# Human_Interface.net
KiCad netlist of a schematic drawn in Altium Designer
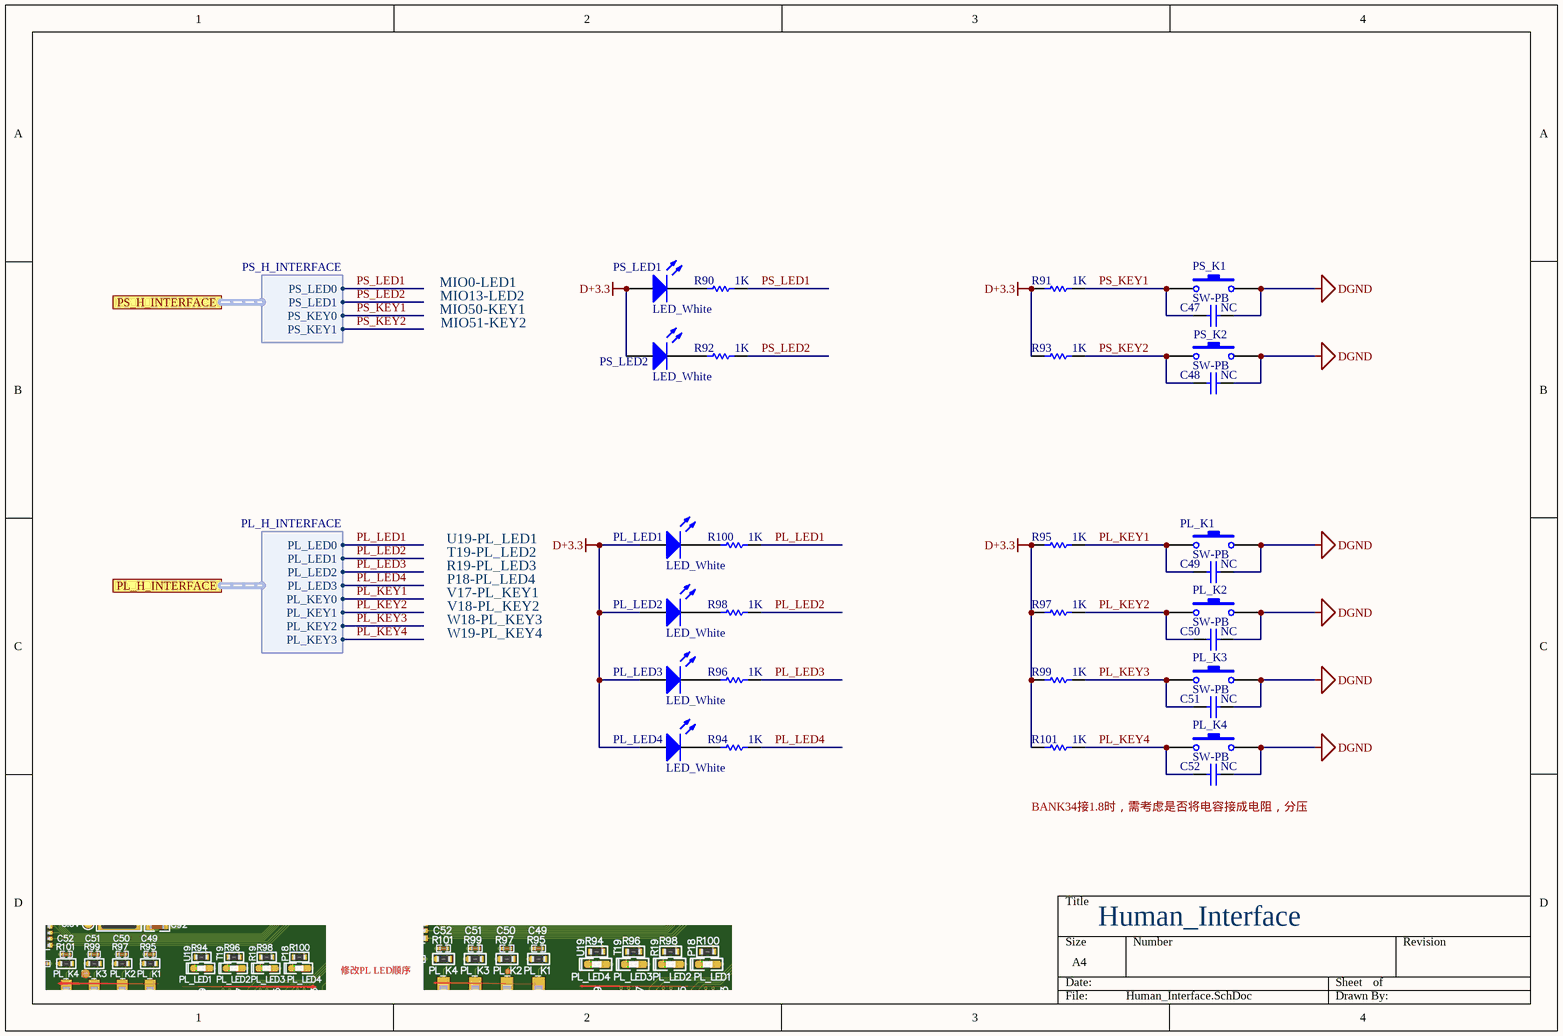
[diagram p0: Human_Interface.SchDoc]

(export (version "E")
  (design (tool "Eeschema 10.0.6"))
  (components
    (comp (ref "C47")
      (value "NC")
      (footprint "C 0402_LL")
      (description "Capacitor")
      (fields (field (name "PUBLISHER") "Altium Limited"))
      (libsource (lib "Miscellaneous Devices") (part "Cap"))
    )
    (comp (ref "C48")
      (value "NC")
      (footprint "C 0402_LL")
      (description "Capacitor")
      (fields (field (name "PUBLISHER") "Altium Limited"))
      (libsource (lib "Miscellaneous Devices") (part "Cap"))
    )
    (comp (ref "C49")
      (value "NC")
      (footprint "C 0402_LL")
      (description "Capacitor")
      (fields (field (name "PUBLISHER") "Altium Limited"))
      (libsource (lib "Miscellaneous Devices") (part "Cap"))
    )
    (comp (ref "C50")
      (value "NC")
      (footprint "C 0402_LL")
      (description "Capacitor")
      (fields (field (name "PUBLISHER") "Altium Limited"))
      (libsource (lib "Miscellaneous Devices") (part "Cap"))
    )
    (comp (ref "C51")
      (value "NC")
      (footprint "C 0402_LL")
      (description "Capacitor")
      (fields (field (name "PUBLISHER") "Altium Limited"))
      (libsource (lib "Miscellaneous Devices") (part "Cap"))
    )
    (comp (ref "C52")
      (value "NC")
      (footprint "C 0402_LL")
      (description "Capacitor")
      (fields (field (name "PUBLISHER") "Altium Limited"))
      (libsource (lib "Miscellaneous Devices") (part "Cap"))
    )
    (comp (ref "PL_K1")
      (value "SW-PB")
      (footprint "TSW SMD-3*6*4.3")
      (description "Switch")
      (fields (field (name "PUBLISHER") "Altium Limited"))
      (libsource (lib "Miscellaneous Devices") (part "SW-PB"))
    )
    (comp (ref "PL_K2")
      (value "SW-PB")
      (footprint "TSW SMD-3*6*4.3")
      (description "Switch")
      (fields (field (name "PUBLISHER") "Altium Limited"))
      (libsource (lib "Miscellaneous Devices") (part "SW-PB"))
    )
    (comp (ref "PL_K3")
      (value "SW-PB")
      (footprint "TSW SMD-3*6*4.3")
      (description "Switch")
      (fields (field (name "PUBLISHER") "Altium Limited"))
      (libsource (lib "Miscellaneous Devices") (part "SW-PB"))
    )
    (comp (ref "PL_K4")
      (value "SW-PB")
      (footprint "TSW SMD-3*6*4.3")
      (description "Switch")
      (fields (field (name "PUBLISHER") "Altium Limited"))
      (libsource (lib "Miscellaneous Devices") (part "SW-PB"))
    )
    (comp (ref "PL_LED1")
      (value "LED_White")
      (footprint "LED 0603W")
      (description "Typical INFRARED GaAs LED")
      (fields (field (name "PUBLISHER") "Altium Limited"))
      (libsource (lib "Miscellaneous Devices") (part "LED0"))
    )
    (comp (ref "PL_LED2")
      (value "LED_White")
      (footprint "LED 0603W")
      (description "Typical INFRARED GaAs LED")
      (fields (field (name "PUBLISHER") "Altium Limited"))
      (libsource (lib "Miscellaneous Devices") (part "LED0"))
    )
    (comp (ref "PL_LED3")
      (value "LED_White")
      (footprint "LED 0603W")
      (description "Typical INFRARED GaAs LED")
      (fields (field (name "PUBLISHER") "Altium Limited"))
      (libsource (lib "Miscellaneous Devices") (part "LED0"))
    )
    (comp (ref "PL_LED4")
      (value "LED_White")
      (footprint "LED 0603W")
      (description "Typical INFRARED GaAs LED")
      (fields (field (name "PUBLISHER") "Altium Limited"))
      (libsource (lib "Miscellaneous Devices") (part "LED0"))
    )
    (comp (ref "PS_K1")
      (value "SW-PB")
      (footprint "TSW SMD-3*6*4.3")
      (description "Switch")
      (fields (field (name "PUBLISHER") "Altium Limited"))
      (libsource (lib "Miscellaneous Devices") (part "SW-PB"))
    )
    (comp (ref "PS_K2")
      (value "SW-PB")
      (footprint "TSW SMD-3*6*4.3")
      (description "Switch")
      (fields (field (name "PUBLISHER") "Altium Limited"))
      (libsource (lib "Miscellaneous Devices") (part "SW-PB"))
    )
    (comp (ref "PS_LED1")
      (value "LED_White")
      (footprint "LED 0603W")
      (description "Typical INFRARED GaAs LED")
      (fields (field (name "PUBLISHER") "Altium Limited"))
      (libsource (lib "Miscellaneous Devices") (part "LED0"))
    )
    (comp (ref "PS_LED2")
      (value "LED_White")
      (footprint "LED 0603W")
      (description "Typical INFRARED GaAs LED")
      (fields (field (name "PUBLISHER") "Altium Limited"))
      (libsource (lib "Miscellaneous Devices") (part "LED0"))
    )
    (comp (ref "R90")
      (value "1K")
      (footprint "R 0603_L")
      (description "Resistor")
      (fields (field (name "PUBLISHER") "Altium Limited"))
      (libsource (lib "Miscellaneous Devices") (part "Res1"))
    )
    (comp (ref "R91")
      (value "1K")
      (footprint "R 0603_L")
      (description "Resistor")
      (fields (field (name "PUBLISHER") "Altium Limited"))
      (libsource (lib "Miscellaneous Devices") (part "Res1"))
    )
    (comp (ref "R92")
      (value "1K")
      (footprint "R 0603_L")
      (description "Resistor")
      (fields (field (name "PUBLISHER") "Altium Limited"))
      (libsource (lib "Miscellaneous Devices") (part "Res1"))
    )
    (comp (ref "R93")
      (value "1K")
      (footprint "R 0603_L")
      (description "Resistor")
      (fields (field (name "PUBLISHER") "Altium Limited"))
      (libsource (lib "Miscellaneous Devices") (part "Res1"))
    )
    (comp (ref "R94")
      (value "1K")
      (footprint "R 0603_L")
      (description "Resistor")
      (fields (field (name "PUBLISHER") "Altium Limited"))
      (libsource (lib "Miscellaneous Devices") (part "Res1"))
    )
    (comp (ref "R95")
      (value "1K")
      (footprint "R 0603_L")
      (description "Resistor")
      (fields (field (name "PUBLISHER") "Altium Limited"))
      (libsource (lib "Miscellaneous Devices") (part "Res1"))
    )
    (comp (ref "R96")
      (value "1K")
      (footprint "R 0603_L")
      (description "Resistor")
      (fields (field (name "PUBLISHER") "Altium Limited"))
      (libsource (lib "Miscellaneous Devices") (part "Res1"))
    )
    (comp (ref "R97")
      (value "1K")
      (footprint "R 0603_L")
      (description "Resistor")
      (fields (field (name "PUBLISHER") "Altium Limited"))
      (libsource (lib "Miscellaneous Devices") (part "Res1"))
    )
    (comp (ref "R98")
      (value "1K")
      (footprint "R 0603_L")
      (description "Resistor")
      (fields (field (name "PUBLISHER") "Altium Limited"))
      (libsource (lib "Miscellaneous Devices") (part "Res1"))
    )
    (comp (ref "R99")
      (value "1K")
      (footprint "R 0603_L")
      (description "Resistor")
      (fields (field (name "PUBLISHER") "Altium Limited"))
      (libsource (lib "Miscellaneous Devices") (part "Res1"))
    )
    (comp (ref "R100")
      (value "1K")
      (footprint "R 0603_L")
      (description "Resistor")
      (fields (field (name "PUBLISHER") "Altium Limited"))
      (libsource (lib "Miscellaneous Devices") (part "Res1"))
    )
    (comp (ref "R101")
      (value "1K")
      (footprint "R 0603_L")
      (description "Resistor")
      (fields (field (name "PUBLISHER") "Altium Limited"))
      (libsource (lib "Miscellaneous Devices") (part "Res1"))
    )
  )
  (nets
    (net (code "3") (name "/PL_KEY1") (class "Default")
      (node (ref "C49") (pin "2") (pinfunction "2_2") (pintype "passive"))
      (node (ref "PL_K1") (pin "1") (pinfunction "1_1") (pintype "passive"))
      (node (ref "R95") (pin "1") (pinfunction "1_1") (pintype "passive"))
    )
    (net (code "4") (name "/PL_KEY2") (class "Default")
      (node (ref "C50") (pin "2") (pinfunction "2_2") (pintype "passive"))
      (node (ref "PL_K2") (pin "1") (pinfunction "1_1") (pintype "passive"))
      (node (ref "R97") (pin "1") (pinfunction "1_1") (pintype "passive"))
    )
    (net (code "5") (name "/PL_KEY3") (class "Default")
      (node (ref "C51") (pin "2") (pinfunction "2_2") (pintype "passive"))
      (node (ref "PL_K3") (pin "1") (pinfunction "1_1") (pintype "passive"))
      (node (ref "R99") (pin "1") (pinfunction "1_1") (pintype "passive"))
    )
    (net (code "6") (name "/PL_KEY4") (class "Default")
      (node (ref "C52") (pin "2") (pinfunction "2_2") (pintype "passive"))
      (node (ref "PL_K4") (pin "1") (pinfunction "1_1") (pintype "passive"))
      (node (ref "R101") (pin "1") (pinfunction "1_1") (pintype "passive"))
    )
    (net (code "7") (name "/PL_LED1") (class "Default")
      (node (ref "R100") (pin "1") (pinfunction "1_1") (pintype "passive"))
    )
    (net (code "8") (name "/PL_LED2") (class "Default")
      (node (ref "R98") (pin "1") (pinfunction "1_1") (pintype "passive"))
    )
    (net (code "9") (name "/PL_LED3") (class "Default")
      (node (ref "R96") (pin "1") (pinfunction "1_1") (pintype "passive"))
    )
    (net (code "10") (name "/PL_LED4") (class "Default")
      (node (ref "R94") (pin "1") (pinfunction "1_1") (pintype "passive"))
    )
    (net (code "11") (name "/PS_KEY1") (class "Default")
      (node (ref "C47") (pin "2") (pinfunction "2_2") (pintype "passive"))
      (node (ref "PS_K1") (pin "1") (pinfunction "1_1") (pintype "passive"))
      (node (ref "R91") (pin "1") (pinfunction "1_1") (pintype "passive"))
    )
    (net (code "12") (name "/PS_KEY2") (class "Default")
      (node (ref "C48") (pin "2") (pinfunction "2_2") (pintype "passive"))
      (node (ref "PS_K2") (pin "1") (pinfunction "1_1") (pintype "passive"))
      (node (ref "R93") (pin "1") (pinfunction "1_1") (pintype "passive"))
    )
    (net (code "13") (name "/PS_LED1") (class "Default")
      (node (ref "R90") (pin "1") (pinfunction "1_1") (pintype "passive"))
    )
    (net (code "14") (name "/PS_LED2") (class "Default")
      (node (ref "R92") (pin "1") (pinfunction "1_1") (pintype "passive"))
    )
    (net (code "17") (name "D+3.3") (class "Default")
      (node (ref "PL_LED1") (pin "1") (pinfunction "A_1") (pintype "passive"))
      (node (ref "PL_LED2") (pin "1") (pinfunction "A_1") (pintype "passive"))
      (node (ref "PL_LED3") (pin "1") (pinfunction "A_1") (pintype "passive"))
      (node (ref "PL_LED4") (pin "1") (pinfunction "A_1") (pintype "passive"))
      (node (ref "PS_LED1") (pin "1") (pinfunction "A_1") (pintype "passive"))
      (node (ref "PS_LED2") (pin "1") (pinfunction "A_1") (pintype "passive"))
      (node (ref "R101") (pin "2") (pinfunction "2_2") (pintype "passive"))
      (node (ref "R91") (pin "2") (pinfunction "2_2") (pintype "passive"))
      (node (ref "R93") (pin "2") (pinfunction "2_2") (pintype "passive"))
      (node (ref "R95") (pin "2") (pinfunction "2_2") (pintype "passive"))
      (node (ref "R97") (pin "2") (pinfunction "2_2") (pintype "passive"))
      (node (ref "R99") (pin "2") (pinfunction "2_2") (pintype "passive"))
    )
    (net (code "18") (name "DGND") (class "Default")
      (node (ref "C47") (pin "1") (pinfunction "1_1") (pintype "passive"))
      (node (ref "C48") (pin "1") (pinfunction "1_1") (pintype "passive"))
      (node (ref "C49") (pin "1") (pinfunction "1_1") (pintype "passive"))
      (node (ref "C50") (pin "1") (pinfunction "1_1") (pintype "passive"))
      (node (ref "C51") (pin "1") (pinfunction "1_1") (pintype "passive"))
      (node (ref "C52") (pin "1") (pinfunction "1_1") (pintype "passive"))
      (node (ref "PL_K1") (pin "2") (pinfunction "2_2") (pintype "passive"))
      (node (ref "PL_K2") (pin "2") (pinfunction "2_2") (pintype "passive"))
      (node (ref "PL_K3") (pin "2") (pinfunction "2_2") (pintype "passive"))
      (node (ref "PL_K4") (pin "2") (pinfunction "2_2") (pintype "passive"))
      (node (ref "PS_K1") (pin "2") (pinfunction "2_2") (pintype "passive"))
      (node (ref "PS_K2") (pin "2") (pinfunction "2_2") (pintype "passive"))
    )
    (net (code "19") (name "Net-(PL_LED1-K)") (class "Default")
      (node (ref "PL_LED1") (pin "2") (pinfunction "K_2") (pintype "passive"))
      (node (ref "R100") (pin "2") (pinfunction "2_2") (pintype "passive"))
    )
    (net (code "20") (name "Net-(PL_LED2-K)") (class "Default")
      (node (ref "PL_LED2") (pin "2") (pinfunction "K_2") (pintype "passive"))
      (node (ref "R98") (pin "2") (pinfunction "2_2") (pintype "passive"))
    )
    (net (code "21") (name "Net-(PL_LED3-K)") (class "Default")
      (node (ref "PL_LED3") (pin "2") (pinfunction "K_2") (pintype "passive"))
      (node (ref "R96") (pin "2") (pinfunction "2_2") (pintype "passive"))
    )
    (net (code "22") (name "Net-(PL_LED4-K)") (class "Default")
      (node (ref "PL_LED4") (pin "2") (pinfunction "K_2") (pintype "passive"))
      (node (ref "R94") (pin "2") (pinfunction "2_2") (pintype "passive"))
    )
    (net (code "23") (name "Net-(PS_LED1-K)") (class "Default")
      (node (ref "PS_LED1") (pin "2") (pinfunction "K_2") (pintype "passive"))
      (node (ref "R90") (pin "2") (pinfunction "2_2") (pintype "passive"))
    )
    (net (code "24") (name "Net-(PS_LED2-K)") (class "Default")
      (node (ref "PS_LED2") (pin "2") (pinfunction "K_2") (pintype "passive"))
      (node (ref "R92") (pin "2") (pinfunction "2_2") (pintype "passive"))
    )
  )
)
